# pricipialka.net
KiCad netlist of a schematic drawn in Altium Designer
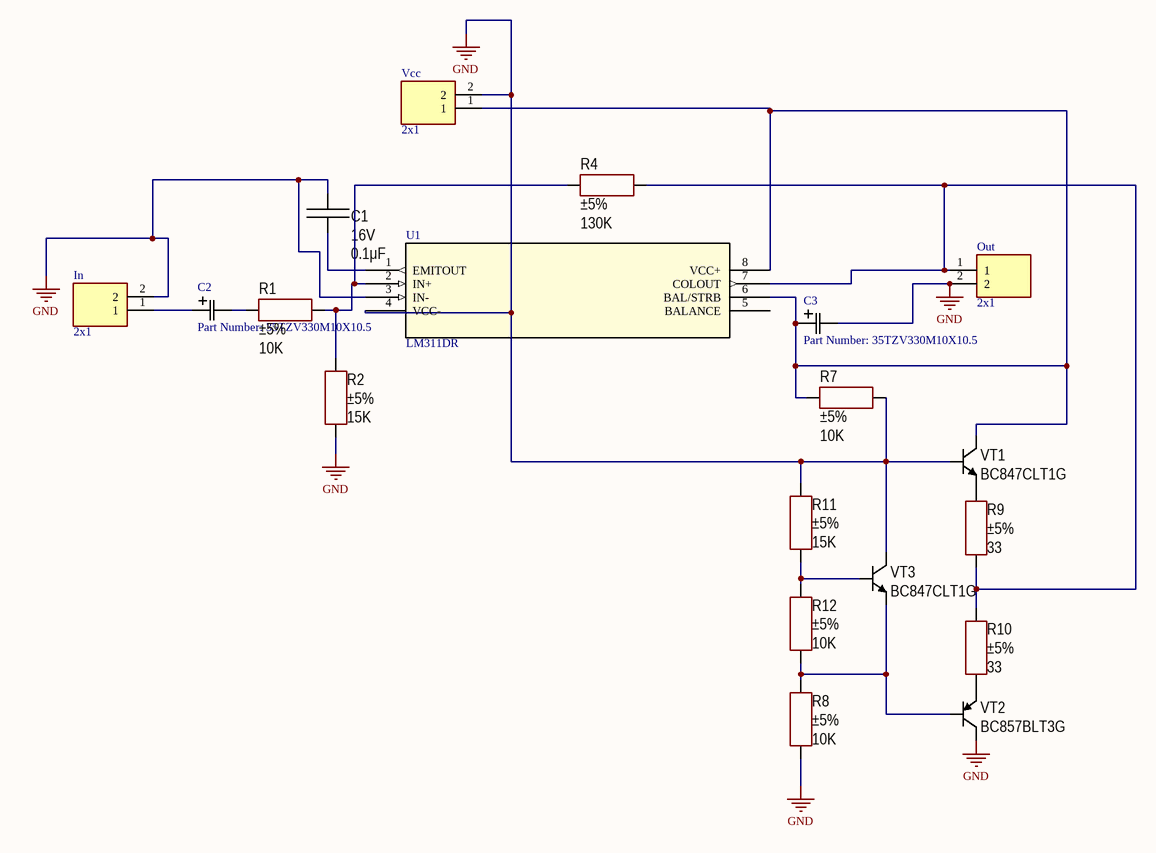
[diagram p0: pricipialka.SchDoc]

(export (version "E")
  (design (tool "Eeschema 10.0.6"))
  (components
    (comp (ref "C1")
      (value "0.1μF")
      (footprint "CAP: 0805")
      (fields
        (field (name "MANUFACTURER") "Yageo")
        (field (name "PARTNUMBER") "CC0805KRX7R7BB104")
        (field (name "VALUEMANUFACTURERPARTNUMBER") "Ceramic capacitor, 0.1μF, X7R, ±10%, 16V, 0805, -55...+125°C")
        (field (name "VOLTAGE") "16V")
      )
      (libsource (lib "Capacitor") (part "Ceramic_0805"))
    )
    (comp (ref "C2")
      (value "Part Number: 35TZV330M10X10.5")
      (footprint "CAP_J-V_10X10P00")
      (description "No Description Available")
      (fields
        (field (name "MANUFACTURER_PART_NUMBER") "35TZV330M10X10.5")
        (field (name "COPYRIGHT") "Copyright (C) 2018 Accelerated Designs. All rights reserved")
      )
      (libsource (lib "SMD Elektrilits") (part "35TZV330M10X10.5"))
    )
    (comp (ref "C3")
      (value "Part Number: 35TZV330M10X10.5")
      (footprint "CAP_J-V_10X10P00")
      (description "No Description Available")
      (fields
        (field (name "MANUFACTURER_PART_NUMBER") "35TZV330M10X10.5")
        (field (name "COPYRIGHT") "Copyright (C) 2018 Accelerated Designs. All rights reserved")
      )
      (libsource (lib "SMD Elektrilits") (part "35TZV330M10X10.5"))
    )
    (comp (ref "In")
      (value "2х1")
      (footprint "2х1 SMD")
      (description "Board-To-Board Connector, Straight, AMPMODU Mod II Series, Through Hole, Header, 2, 2.54 mm")
      (fields (field (name "MP") "826926-2") (field (name "MF") "TE Connectivity"))
      (libsource (lib "SnapEDAsch") (part "2х1"))
    )
    (comp (ref "Out")
      (value "2х1")
      (footprint "2х1 SMD")
      (description "Board-To-Board Connector, Straight, AMPMODU Mod II Series, Through Hole, Header, 2, 2.54 mm")
      (fields (field (name "MP") "826926-2") (field (name "MF") "TE Connectivity"))
      (libsource (lib "") (part "2х1_1"))
    )
    (comp (ref "R1")
      (value "10K")
      (footprint "RES: 0805")
      (fields
        (field (name "MANUFACTURER") "Yageo")
        (field (name "PARTNUMBER") "RC0805JR-07100RL")
        (field (name "VALUEMANUFACTURERPARTNUMBER") "Resistor film, 10K, ±5%, 0805, 0.125W, -55...+125°C")
        (field (name "TOLERANCE") "±5%")
      )
      (libsource (lib "Resistor") (part "Resistor_0805"))
    )
    (comp (ref "R2")
      (value "15K")
      (footprint "RES: 0805")
      (fields
        (field (name "MANUFACTURER") "Yageo")
        (field (name "PARTNUMBER") "RC0805JR-07100RL")
        (field (name "VALUEMANUFACTURERPARTNUMBER") "Resistor film, 15K, ±5%, 0805, 0.125W, -55...+125°C")
        (field (name "TOLERANCE") "±5%")
      )
      (libsource (lib "") (part "Resistor_0805_1"))
    )
    (comp (ref "R4")
      (value "130K")
      (footprint "RES: 0805")
      (fields
        (field (name "MANUFACTURER") "Yageo")
        (field (name "PARTNUMBER") "RC0805JR-07100RL")
        (field (name "VALUEMANUFACTURERPARTNUMBER") "Resistor film, 130K, ±5%, 0805, 0.125W, -55...+125°C")
        (field (name "TOLERANCE") "±5%")
      )
      (libsource (lib "Resistor") (part "Resistor_0805"))
    )
    (comp (ref "R7")
      (value "10K")
      (footprint "RES: 0805")
      (fields
        (field (name "MANUFACTURER") "Yageo")
        (field (name "PARTNUMBER") "RC0805JR-07100RL")
        (field (name "VALUEMANUFACTURERPARTNUMBER") "Resistor film, 10K, ±5%, 0805, 0.125W, -55...+125°C")
        (field (name "TOLERANCE") "±5%")
      )
      (libsource (lib "Resistor") (part "Resistor_0805"))
    )
    (comp (ref "R8")
      (value "10K")
      (footprint "RES: 0805")
      (fields
        (field (name "MANUFACTURER") "Yageo")
        (field (name "PARTNUMBER") "RC0805JR-07100RL")
        (field (name "VALUEMANUFACTURERPARTNUMBER") "Resistor film, 10K, ±5%, 0805, 0.125W, -55...+125°C")
        (field (name "TOLERANCE") "±5%")
      )
      (libsource (lib "") (part "Resistor_0805_1"))
    )
    (comp (ref "R9")
      (value "33")
      (footprint "RES: 0805")
      (fields
        (field (name "MANUFACTURER") "Yageo")
        (field (name "PARTNUMBER") "RC0805JR-07100RL")
        (field (name "VALUEMANUFACTURERPARTNUMBER") "Resistor film, 33, ±5%, 0805, 0.125W, -55...+125°C")
        (field (name "TOLERANCE") "±5%")
      )
      (libsource (lib "") (part "Resistor_0805_1"))
    )
    (comp (ref "R10")
      (value "33")
      (footprint "RES: 0805")
      (fields
        (field (name "MANUFACTURER") "Yageo")
        (field (name "PARTNUMBER") "RC0805JR-07100RL")
        (field (name "VALUEMANUFACTURERPARTNUMBER") "Resistor film, 33, ±5%, 0805, 0.125W, -55...+125°C")
        (field (name "TOLERANCE") "±5%")
      )
      (libsource (lib "") (part "Resistor_0805_1"))
    )
    (comp (ref "R11")
      (value "15K")
      (footprint "RES: 0805")
      (fields
        (field (name "MANUFACTURER") "Yageo")
        (field (name "PARTNUMBER") "RC0805JR-07100RL")
        (field (name "VALUEMANUFACTURERPARTNUMBER") "Resistor film, 15K, ±5%, 0805, 0.125W, -55...+125°C")
        (field (name "TOLERANCE") "±5%")
      )
      (libsource (lib "") (part "Resistor_0805_1"))
    )
    (comp (ref "R12")
      (value "10K")
      (footprint "RES: 0805")
      (fields
        (field (name "MANUFACTURER") "Yageo")
        (field (name "PARTNUMBER") "RC0805JR-07100RL")
        (field (name "VALUEMANUFACTURERPARTNUMBER") "Resistor film, 10K, ±5%, 0805, 0.125W, -55...+125°C")
        (field (name "TOLERANCE") "±5%")
      )
      (libsource (lib "") (part "Resistor_0805_1"))
    )
    (comp (ref "U1")
      (value "LM311DR")
      (footprint "D8")
      (description "Differential Comparator With Strobes")
      (fields
        (field (name "MANUFACTURER") "Texas Instruments")
        (field (name "GENERIC_PART_NUMBER") "LM311")
        (field (name "COPYRIGHT") "Copyright (C) 2018 Accelerated Designs. All rights reserved")
      )
      (libsource (lib "LM311DR") (part "LM311DR"))
    )
    (comp (ref "Vcc")
      (value "2х1")
      (footprint "2х1 SMD")
      (description "Board-To-Board Connector, Straight, AMPMODU Mod II Series, Through Hole, Header, 2, 2.54 mm")
      (fields (field (name "MP") "826926-2") (field (name "MF") "TE Connectivity"))
      (libsource (lib "SnapEDAsch") (part "2х1"))
    )
    (comp (ref "VT1")
      (value "~")
      (footprint "SOT23")
      (fields
        (field (name "MANUFACTURER") "ON Semiconductor")
        (field (name "VALUEMANUFACTURERPARTNUMBER") "NPN transistor, 45V, 100mA, 100MHz, 300mW, 0.6V, 420, SOT-23, -55...+125°C")
        (field (name "PARTNUMBER") "BC847CLT1G")
      )
      (libsource (lib "Transistor") (part "BJT_NPN_132"))
    )
    (comp (ref "VT2")
      (value "~")
      (footprint "SOT23")
      (fields
        (field (name "MANUFACTURER") "ON Semiconductor")
        (field (name "VALUEMANUFACTURERPARTNUMBER") "PNP transistor, 45V, 100mA, 100MHz, 300mW, 0.65V, 220, SOT-23, -55...+125°C")
        (field (name "PARTNUMBER") "BC857BLT3G")
      )
      (libsource (lib "Transistor") (part "BJT_PNP_123"))
    )
    (comp (ref "VT3")
      (value "~")
      (footprint "SOT23")
      (fields
        (field (name "MANUFACTURER") "ON Semiconductor")
        (field (name "VALUEMANUFACTURERPARTNUMBER") "NPN transistor, 45V, 100mA, 100MHz, 300mW, 0.6V, 420, SOT-23, -55...+125°C")
        (field (name "PARTNUMBER") "BC847CLT1G")
      )
      (libsource (lib "Transistor") (part "BJT_NPN_132"))
    )
  )
  (nets
    (net (code "1") (name "GND") (class "Default")
      (node (ref "C1") (pin "2") (pinfunction "2_2") (pintype "power_in"))
      (node (ref "C3") (pin "2") (pinfunction "2_2") (pintype "power_in"))
      (node (ref "In") (pin "2") (pinfunction "2_2") (pintype "passive"))
      (node (ref "Out") (pin "2") (pinfunction "2_2") (pintype "passive"))
      (node (ref "R11") (pin "2") (pinfunction "2_2") (pintype "passive"))
      (node (ref "R2") (pin "1") (pinfunction "1_1") (pintype "passive"))
      (node (ref "R7") (pin "2") (pinfunction "2_2") (pintype "passive"))
      (node (ref "R8") (pin "1") (pinfunction "1_1") (pintype "passive"))
      (node (ref "U1") (pin "3") (pinfunction "IN-_3") (pintype "input"))
      (node (ref "U1") (pin "4") (pinfunction "VCC-_4") (pintype "power_in"))
      (node (ref "VT1") (pin "1") (pinfunction "B_1") (pintype "passive"))
      (node (ref "VT2") (pin "3") (pinfunction "C_3") (pintype "passive"))
      (node (ref "VT3") (pin "3") (pinfunction "C_3") (pintype "passive"))
      (node (ref "Vcc") (pin "2") (pinfunction "2_2") (pintype "passive"))
    )
    (net (code "2") (name "Net-(C2-Pad1)") (class "Default")
      (node (ref "C2") (pin "1") (pinfunction "1_1") (pintype "power_in"))
      (node (ref "In") (pin "1") (pinfunction "1_1") (pintype "passive"))
    )
    (net (code "3") (name "Net-(C2-Pad2)") (class "Default")
      (node (ref "C2") (pin "2") (pinfunction "2_2") (pintype "power_in"))
      (node (ref "R1") (pin "1") (pinfunction "1_1") (pintype "passive"))
    )
    (net (code "4") (name "Net-(U1-BAL{slash}STRB)") (class "Default")
      (node (ref "C3") (pin "1") (pinfunction "1_1") (pintype "power_in"))
      (node (ref "R7") (pin "1") (pinfunction "1_1") (pintype "passive"))
      (node (ref "U1") (pin "6") (pinfunction "BAL/STRB_6") (pintype "passive"))
      (node (ref "U1") (pin "8") (pinfunction "VCC+_8") (pintype "power_in"))
      (node (ref "VT1") (pin "3") (pinfunction "C_3") (pintype "passive"))
      (node (ref "Vcc") (pin "1") (pinfunction "1_1") (pintype "passive"))
    )
    (net (code "5") (name "Net-(U1-COLOUT)") (class "Default")
      (node (ref "Out") (pin "1") (pinfunction "1_1") (pintype "passive"))
      (node (ref "R10") (pin "2") (pinfunction "2_2") (pintype "passive"))
      (node (ref "R4") (pin "2") (pinfunction "2_2") (pintype "passive"))
      (node (ref "R9") (pin "1") (pinfunction "1_1") (pintype "passive"))
      (node (ref "U1") (pin "7") (pinfunction "COLOUT_7") (pintype "output"))
    )
    (net (code "6") (name "Net-(U1-EMITOUT)") (class "Default")
      (node (ref "C1") (pin "1") (pinfunction "1_1") (pintype "power_in"))
      (node (ref "U1") (pin "1") (pinfunction "EMITOUT_1") (pintype "output"))
    )
    (net (code "7") (name "Net-(U1-IN+)") (class "Default")
      (node (ref "R1") (pin "2") (pinfunction "2_2") (pintype "passive"))
      (node (ref "R2") (pin "2") (pinfunction "2_2") (pintype "passive"))
      (node (ref "R4") (pin "1") (pinfunction "1_1") (pintype "passive"))
      (node (ref "U1") (pin "2") (pinfunction "IN+_2") (pintype "input"))
    )
    (net (code "8") (name "Net-(VT1-E)") (class "Default")
      (node (ref "R9") (pin "2") (pinfunction "2_2") (pintype "passive"))
      (node (ref "VT1") (pin "2") (pinfunction "E_2") (pintype "passive"))
    )
    (net (code "9") (name "Net-(VT2-B)") (class "Default")
      (node (ref "R12") (pin "1") (pinfunction "1_1") (pintype "passive"))
      (node (ref "R8") (pin "2") (pinfunction "2_2") (pintype "passive"))
      (node (ref "VT2") (pin "1") (pinfunction "B_1") (pintype "passive"))
      (node (ref "VT3") (pin "2") (pinfunction "E_2") (pintype "passive"))
    )
    (net (code "10") (name "Net-(VT2-E)") (class "Default")
      (node (ref "R10") (pin "1") (pinfunction "1_1") (pintype "passive"))
      (node (ref "VT2") (pin "2") (pinfunction "E_2") (pintype "passive"))
    )
    (net (code "11") (name "Net-(VT3-B)") (class "Default")
      (node (ref "R11") (pin "1") (pinfunction "1_1") (pintype "passive"))
      (node (ref "R12") (pin "2") (pinfunction "2_2") (pintype "passive"))
      (node (ref "VT3") (pin "1") (pinfunction "B_1") (pintype "passive"))
    )
    (net (code "12") (name "unconnected-(U1-BALANCE-Pad5)") (class "Default")
      (node (ref "U1") (pin "5") (pinfunction "BALANCE_5") (pintype "passive"))
    )
  )
)
